# Sheet1.net
KiCad netlist of a schematic drawn in Altium Designer
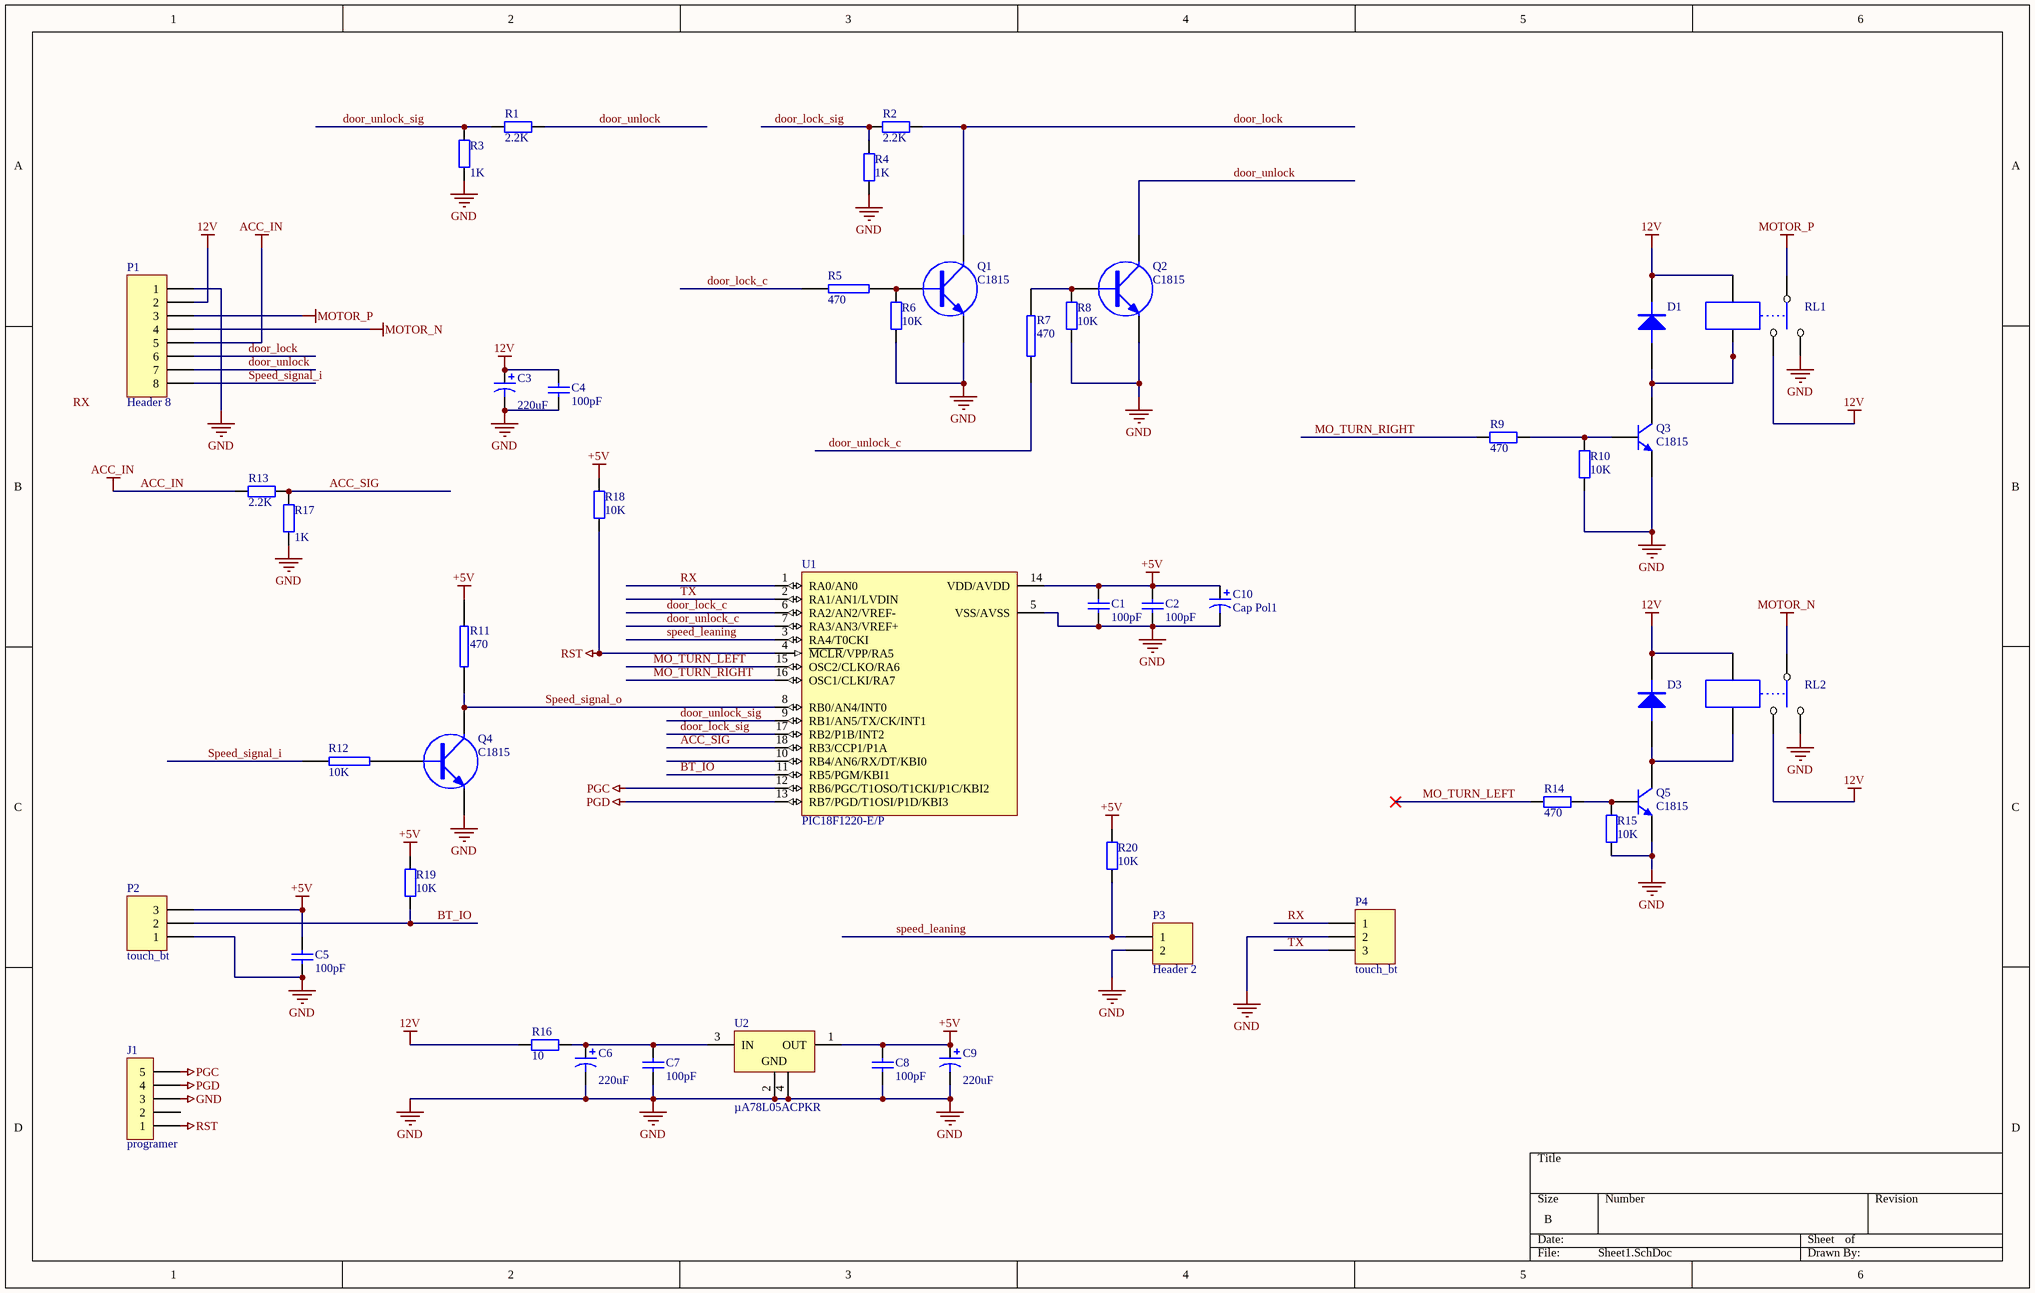
[diagram p0: Sheet1.SchDoc]

(export (version "E")
  (design (tool "Eeschema 10.0.6"))
  (components
    (comp (ref "C1")
      (value "100pF")
      (footprint "RESC2012L")
      (description "Capacitor (Semiconductor SIM Model)")
      (fields (field (name "Comment") "Cap Semi") (field (name "PUBLISHER") "Altium Limited"))
      (libsource (lib "Miscellaneous Devices") (part "Cap Semi"))
    )
    (comp (ref "C2")
      (value "100pF")
      (footprint "RESC2012L")
      (description "Capacitor (Semiconductor SIM Model)")
      (fields (field (name "Comment") "Cap Semi") (field (name "PUBLISHER") "Altium Limited"))
      (libsource (lib "Miscellaneous Devices") (part "Cap Semi"))
    )
    (comp (ref "C3")
      (value "220uF")
      (footprint "CAPU150-175K")
      (description "Polarized Capacitor (Surface Mount)")
      (fields (field (name "Comment") "Cap Pol3") (field (name "PUBLISHER") "Altium Limited"))
      (libsource (lib "Miscellaneous Devices") (part "Cap Pol3"))
    )
    (comp (ref "C4")
      (value "100pF")
      (footprint "RESC2012L")
      (description "Capacitor (Semiconductor SIM Model)")
      (fields (field (name "Comment") "Cap Semi") (field (name "PUBLISHER") "Altium Limited"))
      (libsource (lib "Miscellaneous Devices") (part "Cap Semi"))
    )
    (comp (ref "C5")
      (value "100pF")
      (footprint "RESC2012L")
      (description "Capacitor (Semiconductor SIM Model)")
      (fields (field (name "Comment") "Cap Semi") (field (name "PUBLISHER") "Altium Limited"))
      (libsource (lib "Miscellaneous Devices") (part "Cap Semi"))
    )
    (comp (ref "C6")
      (value "220uF")
      (footprint "CAPU150-175K")
      (description "Polarized Capacitor (Surface Mount)")
      (fields (field (name "Comment") "Cap Pol3") (field (name "PUBLISHER") "Altium Limited"))
      (libsource (lib "Miscellaneous Devices") (part "Cap Pol3"))
    )
    (comp (ref "C7")
      (value "100pF")
      (footprint "RESC2012L")
      (description "Capacitor (Semiconductor SIM Model)")
      (fields (field (name "Comment") "Cap Semi") (field (name "PUBLISHER") "Altium Limited"))
      (libsource (lib "Miscellaneous Devices") (part "Cap Semi"))
    )
    (comp (ref "C8")
      (value "100pF")
      (footprint "RESC2012L")
      (description "Capacitor (Semiconductor SIM Model)")
      (fields (field (name "Comment") "Cap Semi") (field (name "PUBLISHER") "Altium Limited"))
      (libsource (lib "Miscellaneous Devices") (part "Cap Semi"))
    )
    (comp (ref "C9")
      (value "220uF")
      (footprint "CAPU150-175K")
      (description "Polarized Capacitor (Surface Mount)")
      (fields (field (name "Comment") "Cap Pol3") (field (name "PUBLISHER") "Altium Limited"))
      (libsource (lib "Miscellaneous Devices") (part "Cap Pol3"))
    )
    (comp (ref "C10")
      (value "Cap Pol1")
      (footprint "CAP5")
      (description "Polarized Capacitor (Radial)")
      (fields (field (name "PUBLISHER") "Altium Limited"))
      (libsource (lib "Miscellaneous Devices") (part "Cap Pol1"))
    )
    (comp (ref "D1") (value "~") (footprint "D1A") (description "Diode") (libsource (lib "*") (part "DIODE")))
    (comp (ref "D3") (value "~") (footprint "D1A") (description "Diode") (libsource (lib "*") (part "DIODE")))
    (comp (ref "J1")
      (value "programer")
      (footprint "HDR1x5")
      (description "Connector")
      (libsource (lib "*") (part "CON5"))
    )
    (comp (ref "P1")
      (value "Header 8")
      (footprint "P8_150")
      (description "Header, 8-Pin")
      (fields (field (name "PUBLISHER") "Altium Limited"))
      (libsource (lib "Miscellaneous Connectors") (part "Header 8"))
    )
    (comp (ref "P2")
      (value "touch_bt")
      (footprint "HDR1X3")
      (description "Header, 3-Pin")
      (fields (field (name "PUBLISHER") "Altium Limited"))
      (libsource (lib "") (part "Header 3_1"))
    )
    (comp (ref "P3")
      (value "Header 2")
      (footprint "HDR1X2")
      (description "Header, 2-Pin")
      (fields (field (name "PUBLISHER") "Altium Limited"))
      (libsource (lib "Miscellaneous Connectors") (part "Header 2"))
    )
    (comp (ref "P4")
      (value "touch_bt")
      (footprint "HDR1X3")
      (description "Header, 3-Pin")
      (fields (field (name "PUBLISHER") "Altium Limited"))
      (libsource (lib "Miscellaneous Connectors") (part "Header 3"))
    )
    (comp (ref "Q1")
      (value "C1815")
      (footprint "C1815")
      (description "NPN Transistor")
      (libsource (lib "") (part "NPN_1"))
    )
    (comp (ref "Q2")
      (value "C1815")
      (footprint "C1815")
      (description "NPN Transistor")
      (libsource (lib "") (part "NPN_1"))
    )
    (comp (ref "Q3")
      (value "C1815")
      (footprint "C1815")
      (description "NPN Transistor")
      (libsource (lib "Schlib1") (part "NPN"))
    )
    (comp (ref "Q4")
      (value "C1815")
      (footprint "C1815")
      (description "NPN Transistor")
      (libsource (lib "") (part "NPN_1"))
    )
    (comp (ref "Q5")
      (value "C1815")
      (footprint "C1815")
      (description "NPN Transistor")
      (libsource (lib "Schlib1") (part "NPN"))
    )
    (comp (ref "R1")
      (value "2.2K")
      (footprint "RESC2012L")
      (description "Resistor")
      (fields (field (name "Comment") "Res2") (field (name "PUBLISHER") "Altium Limited"))
      (libsource (lib "Miscellaneous Devices") (part "Res2"))
    )
    (comp (ref "R2")
      (value "2.2K")
      (footprint "RESC2012L")
      (description "Resistor")
      (fields (field (name "Comment") "Res2") (field (name "PUBLISHER") "Altium Limited"))
      (libsource (lib "Miscellaneous Devices") (part "Res2"))
    )
    (comp (ref "R3")
      (value "1K")
      (footprint "RESC2012L")
      (description "Resistor")
      (fields (field (name "Comment") "Res2") (field (name "PUBLISHER") "Altium Limited"))
      (libsource (lib "") (part "Res2_1"))
    )
    (comp (ref "R4")
      (value "1K")
      (footprint "RESC2012L")
      (description "Resistor")
      (fields (field (name "Comment") "Res2") (field (name "PUBLISHER") "Altium Limited"))
      (libsource (lib "") (part "Res2_2"))
    )
    (comp (ref "R5") (value "470") (footprint "RESC2012L") (libsource (lib "*") (part "RES2")))
    (comp (ref "R6")
      (value "10K")
      (footprint "RESC2012L")
      (description "Resistor")
      (fields (field (name "Comment") "Res2") (field (name "PUBLISHER") "Altium Limited"))
      (libsource (lib "") (part "Res2_2"))
    )
    (comp (ref "R7") (value "470") (footprint "RESC2012L") (libsource (lib "*") (part "RES2")))
    (comp (ref "R8")
      (value "10K")
      (footprint "RESC2012L")
      (description "Resistor")
      (fields (field (name "Comment") "Res2") (field (name "PUBLISHER") "Altium Limited"))
      (libsource (lib "") (part "Res2_2"))
    )
    (comp (ref "R9")
      (value "470")
      (footprint "RESC2012L")
      (description "Resistor")
      (fields (field (name "Comment") "Res2") (field (name "PUBLISHER") "Altium Limited"))
      (libsource (lib "Miscellaneous Devices") (part "Res2"))
    )
    (comp (ref "R10")
      (value "10K")
      (footprint "RESC2012L")
      (description "Resistor")
      (fields (field (name "Comment") "Res2") (field (name "PUBLISHER") "Altium Limited"))
      (libsource (lib "") (part "Res2_2"))
    )
    (comp (ref "R11") (value "470") (footprint "RESC2012L") (libsource (lib "*") (part "RES2")))
    (comp (ref "R12") (value "10K") (footprint "RESC2012L") (libsource (lib "*") (part "RES2")))
    (comp (ref "R13")
      (value "2.2K")
      (footprint "RESC2012L")
      (description "Resistor")
      (fields (field (name "Comment") "Res2") (field (name "PUBLISHER") "Altium Limited"))
      (libsource (lib "Miscellaneous Devices") (part "Res2"))
    )
    (comp (ref "R14")
      (value "470")
      (footprint "RESC2012L")
      (description "Resistor")
      (fields (field (name "Comment") "Res2") (field (name "PUBLISHER") "Altium Limited"))
      (libsource (lib "Miscellaneous Devices") (part "Res2"))
    )
    (comp (ref "R15")
      (value "10K")
      (footprint "RESC2012L")
      (description "Resistor")
      (fields (field (name "Comment") "Res2") (field (name "PUBLISHER") "Altium Limited"))
      (libsource (lib "") (part "Res2_2"))
    )
    (comp (ref "R16")
      (value "10")
      (footprint "R1W-600")
      (description "Resistor")
      (fields (field (name "Comment") "Res2") (field (name "PUBLISHER") "Altium Limited"))
      (libsource (lib "Miscellaneous Devices") (part "Res2"))
    )
    (comp (ref "R17")
      (value "1K")
      (footprint "RESC2012L")
      (description "Resistor")
      (fields (field (name "Comment") "Res2") (field (name "PUBLISHER") "Altium Limited"))
      (libsource (lib "") (part "Res2_1"))
    )
    (comp (ref "R18")
      (value "10K")
      (footprint "RESC2012L")
      (description "Resistor")
      (fields (field (name "Comment") "Res2") (field (name "PUBLISHER") "Altium Limited"))
      (libsource (lib "") (part "Res2_2"))
    )
    (comp (ref "R19")
      (value "10K")
      (footprint "RESC2012L")
      (description "Resistor")
      (fields (field (name "Comment") "Res2") (field (name "PUBLISHER") "Altium Limited"))
      (libsource (lib "") (part "Res2_2"))
    )
    (comp (ref "R20")
      (value "10K")
      (footprint "RESC2012L")
      (description "Resistor")
      (fields (field (name "Comment") "Res2") (field (name "PUBLISHER") "Altium Limited"))
      (libsource (lib "") (part "Res2_2"))
    )
    (comp (ref "RL1") (value "~") (footprint "RL7") (libsource (lib "*") (part "RELAY-SPDT")))
    (comp (ref "RL2") (value "~") (footprint "RL7") (libsource (lib "*") (part "RELAY-SPDT")))
    (comp (ref "U1")
      (value "PIC18F1220-E/P")
      (footprint "PDIP300-P18")
      (fields (field (name "PUBLISHER") "Altium Limited"))
      (libsource (lib "Microchip Microcontroller 8-Bit PIC18") (part "PIC18F1220-E/P"))
    )
    (comp (ref "U2")
      (value "µA78L05ACPKR")
      (footprint "PK03")
      (description "Positive-Voltage Regulator")
      (fields (field (name "PUBLISHER") "Altium Limited"))
      (libsource (lib "Schlib1") (part "µA78L05ACPKR"))
    )
  )
  (nets
    (net (code "1") (name "+5V") (class "Default")
      (node (ref "C1") (pin "2") (pinfunction "2_2") (pintype "passive"))
      (node (ref "C10") (pin "1") (pinfunction "1_1") (pintype "passive"))
      (node (ref "C2") (pin "2") (pinfunction "2_2") (pintype "passive"))
      (node (ref "C5") (pin "2") (pinfunction "2_2") (pintype "passive"))
      (node (ref "C8") (pin "2") (pinfunction "2_2") (pintype "passive"))
      (node (ref "C9") (pin "1") (pinfunction "1_1") (pintype "passive"))
      (node (ref "P2") (pin "3") (pinfunction "3_3") (pintype "passive"))
      (node (ref "R11") (pin "1") (pinfunction "1_1") (pintype "passive"))
      (node (ref "R18") (pin "1") (pinfunction "1_1") (pintype "passive"))
      (node (ref "R19") (pin "1") (pinfunction "1_1") (pintype "passive"))
      (node (ref "R20") (pin "1") (pinfunction "1_1") (pintype "passive"))
      (node (ref "U1") (pin "14") (pinfunction "VDD/AVDD_14") (pintype "power_in"))
      (node (ref "U2") (pin "1") (pinfunction "OUT_1") (pintype "power_in"))
    )
    (net (code "2") (name "/ACC_SIG") (class "Default")
      (node (ref "R13") (pin "1") (pinfunction "1_1") (pintype "passive"))
      (node (ref "R17") (pin "2") (pinfunction "2_2") (pintype "passive"))
      (node (ref "U1") (pin "18") (pinfunction "RB3/CCP1/P1A_18") (pintype "bidirectional"))
    )
    (net (code "3") (name "/BT_IO") (class "Default")
      (node (ref "P2") (pin "2") (pinfunction "2_2") (pintype "passive"))
      (node (ref "R19") (pin "2") (pinfunction "2_2") (pintype "passive"))
      (node (ref "U1") (pin "11") (pinfunction "RB5/PGM/KBI1_11") (pintype "bidirectional"))
    )
    (net (code "4") (name "/MO_TURN_LEFT") (class "Default")
      (node (ref "R14") (pin "2") (pinfunction "2_2") (pintype "passive"))
      (node (ref "U1") (pin "15") (pinfunction "OSC2/CLKO/RA6_15") (pintype "bidirectional"))
    )
    (net (code "5") (name "/MO_TURN_RIGHT") (class "Default")
      (node (ref "R9") (pin "2") (pinfunction "2_2") (pintype "passive"))
      (node (ref "U1") (pin "16") (pinfunction "OSC1/CLKI/RA7_16") (pintype "bidirectional"))
    )
    (net (code "6") (name "/RX") (class "Default")
      (node (ref "P4") (pin "1") (pinfunction "1_1") (pintype "passive"))
      (node (ref "U1") (pin "1") (pinfunction "RA0/AN0_1") (pintype "bidirectional"))
    )
    (net (code "7") (name "/Speed_signal_i") (class "Default")
      (node (ref "P1") (pin "8") (pinfunction "8_8") (pintype "passive"))
      (node (ref "R12") (pin "1") (pinfunction "1_1") (pintype "passive"))
    )
    (net (code "8") (name "/Speed_signal_o") (class "Default")
      (node (ref "Q4") (pin "2") (pinfunction "C_2") (pintype "passive"))
      (node (ref "R11") (pin "2") (pinfunction "2_2") (pintype "passive"))
      (node (ref "U1") (pin "8") (pinfunction "RB0/AN4/INT0_8") (pintype "bidirectional"))
    )
    (net (code "9") (name "/TX") (class "Default")
      (node (ref "P4") (pin "3") (pinfunction "3_3") (pintype "passive"))
      (node (ref "U1") (pin "2") (pinfunction "RA1/AN1/LVDIN_2") (pintype "bidirectional"))
    )
    (net (code "10") (name "/door_lock") (class "Default")
      (node (ref "P1") (pin "6") (pinfunction "6_6") (pintype "passive"))
      (node (ref "Q1") (pin "2") (pinfunction "C_2") (pintype "passive"))
      (node (ref "R2") (pin "1") (pinfunction "1_1") (pintype "passive"))
    )
    (net (code "11") (name "/door_lock_c") (class "Default")
      (node (ref "R5") (pin "1") (pinfunction "1_1") (pintype "passive"))
      (node (ref "U1") (pin "6") (pinfunction "RA2/AN2/VREF-_6") (pintype "bidirectional"))
    )
    (net (code "12") (name "/door_lock_sig") (class "Default")
      (node (ref "R2") (pin "2") (pinfunction "2_2") (pintype "passive"))
      (node (ref "R4") (pin "1") (pinfunction "1_1") (pintype "passive"))
      (node (ref "U1") (pin "17") (pinfunction "RB2/P1B/INT2_17") (pintype "bidirectional"))
    )
    (net (code "13") (name "/door_unlock") (class "Default")
      (node (ref "P1") (pin "7") (pinfunction "7_7") (pintype "passive"))
      (node (ref "Q2") (pin "2") (pinfunction "C_2") (pintype "passive"))
      (node (ref "R1") (pin "1") (pinfunction "1_1") (pintype "passive"))
    )
    (net (code "14") (name "/door_unlock_c") (class "Default")
      (node (ref "R7") (pin "2") (pinfunction "2_2") (pintype "passive"))
      (node (ref "U1") (pin "7") (pinfunction "RA3/AN3/VREF+_7") (pintype "bidirectional"))
    )
    (net (code "15") (name "/door_unlock_sig") (class "Default")
      (node (ref "R1") (pin "2") (pinfunction "2_2") (pintype "passive"))
      (node (ref "R3") (pin "2") (pinfunction "2_2") (pintype "passive"))
      (node (ref "U1") (pin "9") (pinfunction "RB1/AN5/TX/CK/INT1_9") (pintype "bidirectional"))
    )
    (net (code "16") (name "/speed_leaning") (class "Default")
      (node (ref "P3") (pin "1") (pinfunction "1_1") (pintype "passive"))
      (node (ref "R20") (pin "2") (pinfunction "2_2") (pintype "passive"))
      (node (ref "U1") (pin "3") (pinfunction "RA4/T0CKI_3") (pintype "bidirectional"))
    )
    (net (code "17") (name "12V") (class "Default")
      (node (ref "C3") (pin "1") (pinfunction "1_1") (pintype "passive"))
      (node (ref "C4") (pin "2") (pinfunction "2_2") (pintype "passive"))
      (node (ref "D1") (pin "2") (pinfunction "K_2") (pintype "passive"))
      (node (ref "D3") (pin "2") (pinfunction "K_2") (pintype "passive"))
      (node (ref "P1") (pin "2") (pinfunction "2_2") (pintype "passive"))
      (node (ref "R16") (pin "2") (pinfunction "2_2") (pintype "passive"))
      (node (ref "RL1") (pin "3") (pinfunction "3_3") (pintype "passive"))
      (node (ref "RL1") (pin "4") (pinfunction "4_4") (pintype "passive"))
      (node (ref "RL2") (pin "3") (pinfunction "3_3") (pintype "passive"))
      (node (ref "RL2") (pin "4") (pinfunction "4_4") (pintype "passive"))
    )
    (net (code "18") (name "ACC_IN") (class "Default")
      (node (ref "P1") (pin "5") (pinfunction "5_5") (pintype "passive"))
      (node (ref "R13") (pin "2") (pinfunction "2_2") (pintype "passive"))
    )
    (net (code "19") (name "GND") (class "Default")
      (node (ref "C1") (pin "1") (pinfunction "1_1") (pintype "passive"))
      (node (ref "C10") (pin "2") (pinfunction "2_2") (pintype "passive"))
      (node (ref "C2") (pin "1") (pinfunction "1_1") (pintype "passive"))
      (node (ref "C3") (pin "2") (pinfunction "2_2") (pintype "passive"))
      (node (ref "C4") (pin "1") (pinfunction "1_1") (pintype "passive"))
      (node (ref "C5") (pin "1") (pinfunction "1_1") (pintype "passive"))
      (node (ref "C6") (pin "2") (pinfunction "2_2") (pintype "passive"))
      (node (ref "C7") (pin "1") (pinfunction "1_1") (pintype "passive"))
      (node (ref "C8") (pin "1") (pinfunction "1_1") (pintype "passive"))
      (node (ref "C9") (pin "2") (pinfunction "2_2") (pintype "passive"))
      (node (ref "J1") (pin "3") (pinfunction "3_3") (pintype "passive"))
      (node (ref "P1") (pin "1") (pinfunction "1_1") (pintype "passive"))
      (node (ref "P2") (pin "1") (pinfunction "1_1") (pintype "passive"))
      (node (ref "P3") (pin "2") (pinfunction "2_2") (pintype "passive"))
      (node (ref "P4") (pin "2") (pinfunction "2_2") (pintype "passive"))
      (node (ref "Q1") (pin "3") (pinfunction "E_3") (pintype "passive"))
      (node (ref "Q2") (pin "3") (pinfunction "E_3") (pintype "passive"))
      (node (ref "Q3") (pin "3") (pinfunction "E_3") (pintype "passive"))
      (node (ref "Q4") (pin "3") (pinfunction "E_3") (pintype "passive"))
      (node (ref "Q5") (pin "3") (pinfunction "E_3") (pintype "passive"))
      (node (ref "R10") (pin "2") (pinfunction "2_2") (pintype "passive"))
      (node (ref "R15") (pin "2") (pinfunction "2_2") (pintype "passive"))
      (node (ref "R17") (pin "1") (pinfunction "1_1") (pintype "passive"))
      (node (ref "R3") (pin "1") (pinfunction "1_1") (pintype "passive"))
      (node (ref "R4") (pin "2") (pinfunction "2_2") (pintype "passive"))
      (node (ref "R6") (pin "2") (pinfunction "2_2") (pintype "passive"))
      (node (ref "R8") (pin "2") (pinfunction "2_2") (pintype "passive"))
      (node (ref "RL1") (pin "2") (pinfunction "2_2") (pintype "passive"))
      (node (ref "RL2") (pin "2") (pinfunction "2_2") (pintype "passive"))
      (node (ref "U1") (pin "5") (pinfunction "VSS/AVSS_5") (pintype "power_in"))
      (node (ref "U2") (pin "2") (pinfunction "GND_2") (pintype "power_in"))
      (node (ref "U2") (pin "4") (pinfunction "GND_4") (pintype "power_in"))
    )
    (net (code "20") (name "MOTOR_N") (class "Default")
      (node (ref "P1") (pin "4") (pinfunction "4_4") (pintype "passive"))
      (node (ref "RL2") (pin "1") (pinfunction "1_1") (pintype "passive"))
    )
    (net (code "21") (name "MOTOR_P") (class "Default")
      (node (ref "P1") (pin "3") (pinfunction "3_3") (pintype "passive"))
      (node (ref "RL1") (pin "1") (pinfunction "1_1") (pintype "passive"))
    )
    (net (code "22") (name "Net-(D1-A)") (class "Default")
      (node (ref "D1") (pin "1") (pinfunction "A_1") (pintype "passive"))
      (node (ref "Q3") (pin "2") (pinfunction "C_2") (pintype "passive"))
      (node (ref "RL1") (pin "5") (pinfunction "5_5") (pintype "passive"))
    )
    (net (code "23") (name "Net-(D3-A)") (class "Default")
      (node (ref "D3") (pin "1") (pinfunction "A_1") (pintype "passive"))
      (node (ref "Q5") (pin "2") (pinfunction "C_2") (pintype "passive"))
      (node (ref "RL2") (pin "5") (pinfunction "5_5") (pintype "passive"))
    )
    (net (code "24") (name "Net-(Q1-B)") (class "Default")
      (node (ref "Q1") (pin "1") (pinfunction "B_1") (pintype "passive"))
      (node (ref "R5") (pin "2") (pinfunction "2_2") (pintype "passive"))
      (node (ref "R6") (pin "1") (pinfunction "1_1") (pintype "passive"))
    )
    (net (code "25") (name "Net-(Q2-B)") (class "Default")
      (node (ref "Q2") (pin "1") (pinfunction "B_1") (pintype "passive"))
      (node (ref "R7") (pin "1") (pinfunction "1_1") (pintype "passive"))
      (node (ref "R8") (pin "1") (pinfunction "1_1") (pintype "passive"))
    )
    (net (code "26") (name "Net-(Q3-B)") (class "Default")
      (node (ref "Q3") (pin "1") (pinfunction "B_1") (pintype "passive"))
      (node (ref "R10") (pin "1") (pinfunction "1_1") (pintype "passive"))
      (node (ref "R9") (pin "1") (pinfunction "1_1") (pintype "passive"))
    )
    (net (code "27") (name "Net-(Q4-B)") (class "Default")
      (node (ref "Q4") (pin "1") (pinfunction "B_1") (pintype "passive"))
      (node (ref "R12") (pin "2") (pinfunction "2_2") (pintype "passive"))
    )
    (net (code "28") (name "Net-(Q5-B)") (class "Default")
      (node (ref "Q5") (pin "1") (pinfunction "B_1") (pintype "passive"))
      (node (ref "R14") (pin "1") (pinfunction "1_1") (pintype "passive"))
      (node (ref "R15") (pin "1") (pinfunction "1_1") (pintype "passive"))
    )
    (net (code "29") (name "Net-(U2-IN)") (class "Default")
      (node (ref "C6") (pin "1") (pinfunction "1_1") (pintype "passive"))
      (node (ref "C7") (pin "2") (pinfunction "2_2") (pintype "passive"))
      (node (ref "R16") (pin "1") (pinfunction "1_1") (pintype "passive"))
      (node (ref "U2") (pin "3") (pinfunction "IN_3") (pintype "power_in"))
    )
    (net (code "30") (name "PGC") (class "Default")
      (node (ref "J1") (pin "5") (pinfunction "5_5") (pintype "passive"))
      (node (ref "U1") (pin "12") (pinfunction "RB6/PGC/T1OSO/T1CKI/P1C/KBI2_12") (pintype "bidirectional"))
    )
    (net (code "31") (name "PGD") (class "Default")
      (node (ref "J1") (pin "4") (pinfunction "4_4") (pintype "passive"))
      (node (ref "U1") (pin "13") (pinfunction "RB7/PGD/T1OSI/P1D/KBI3_13") (pintype "bidirectional"))
    )
    (net (code "32") (name "RST") (class "Default")
      (node (ref "J1") (pin "1") (pinfunction "1_1") (pintype "passive"))
      (node (ref "R18") (pin "2") (pinfunction "2_2") (pintype "passive"))
      (node (ref "U1") (pin "4") (pinfunction "~{MCLR}/VPP/RA5_4") (pintype "input"))
    )
    (net (code "33") (name "unconnected-(J1-Pad2)") (class "Default")
      (node (ref "J1") (pin "2") (pinfunction "2_2") (pintype "passive"))
    )
    (net (code "34") (name "unconnected-(U1-RB4{slash}AN6{slash}RX{slash}DT{slash}KBI0-Pad10)") (class "Default")
      (node (ref "U1") (pin "10") (pinfunction "RB4/AN6/RX/DT/KBI0_10") (pintype "bidirectional"))
    )
  )
)
